# Sheet1.net
KiCad netlist of a schematic drawn in Altium Designer
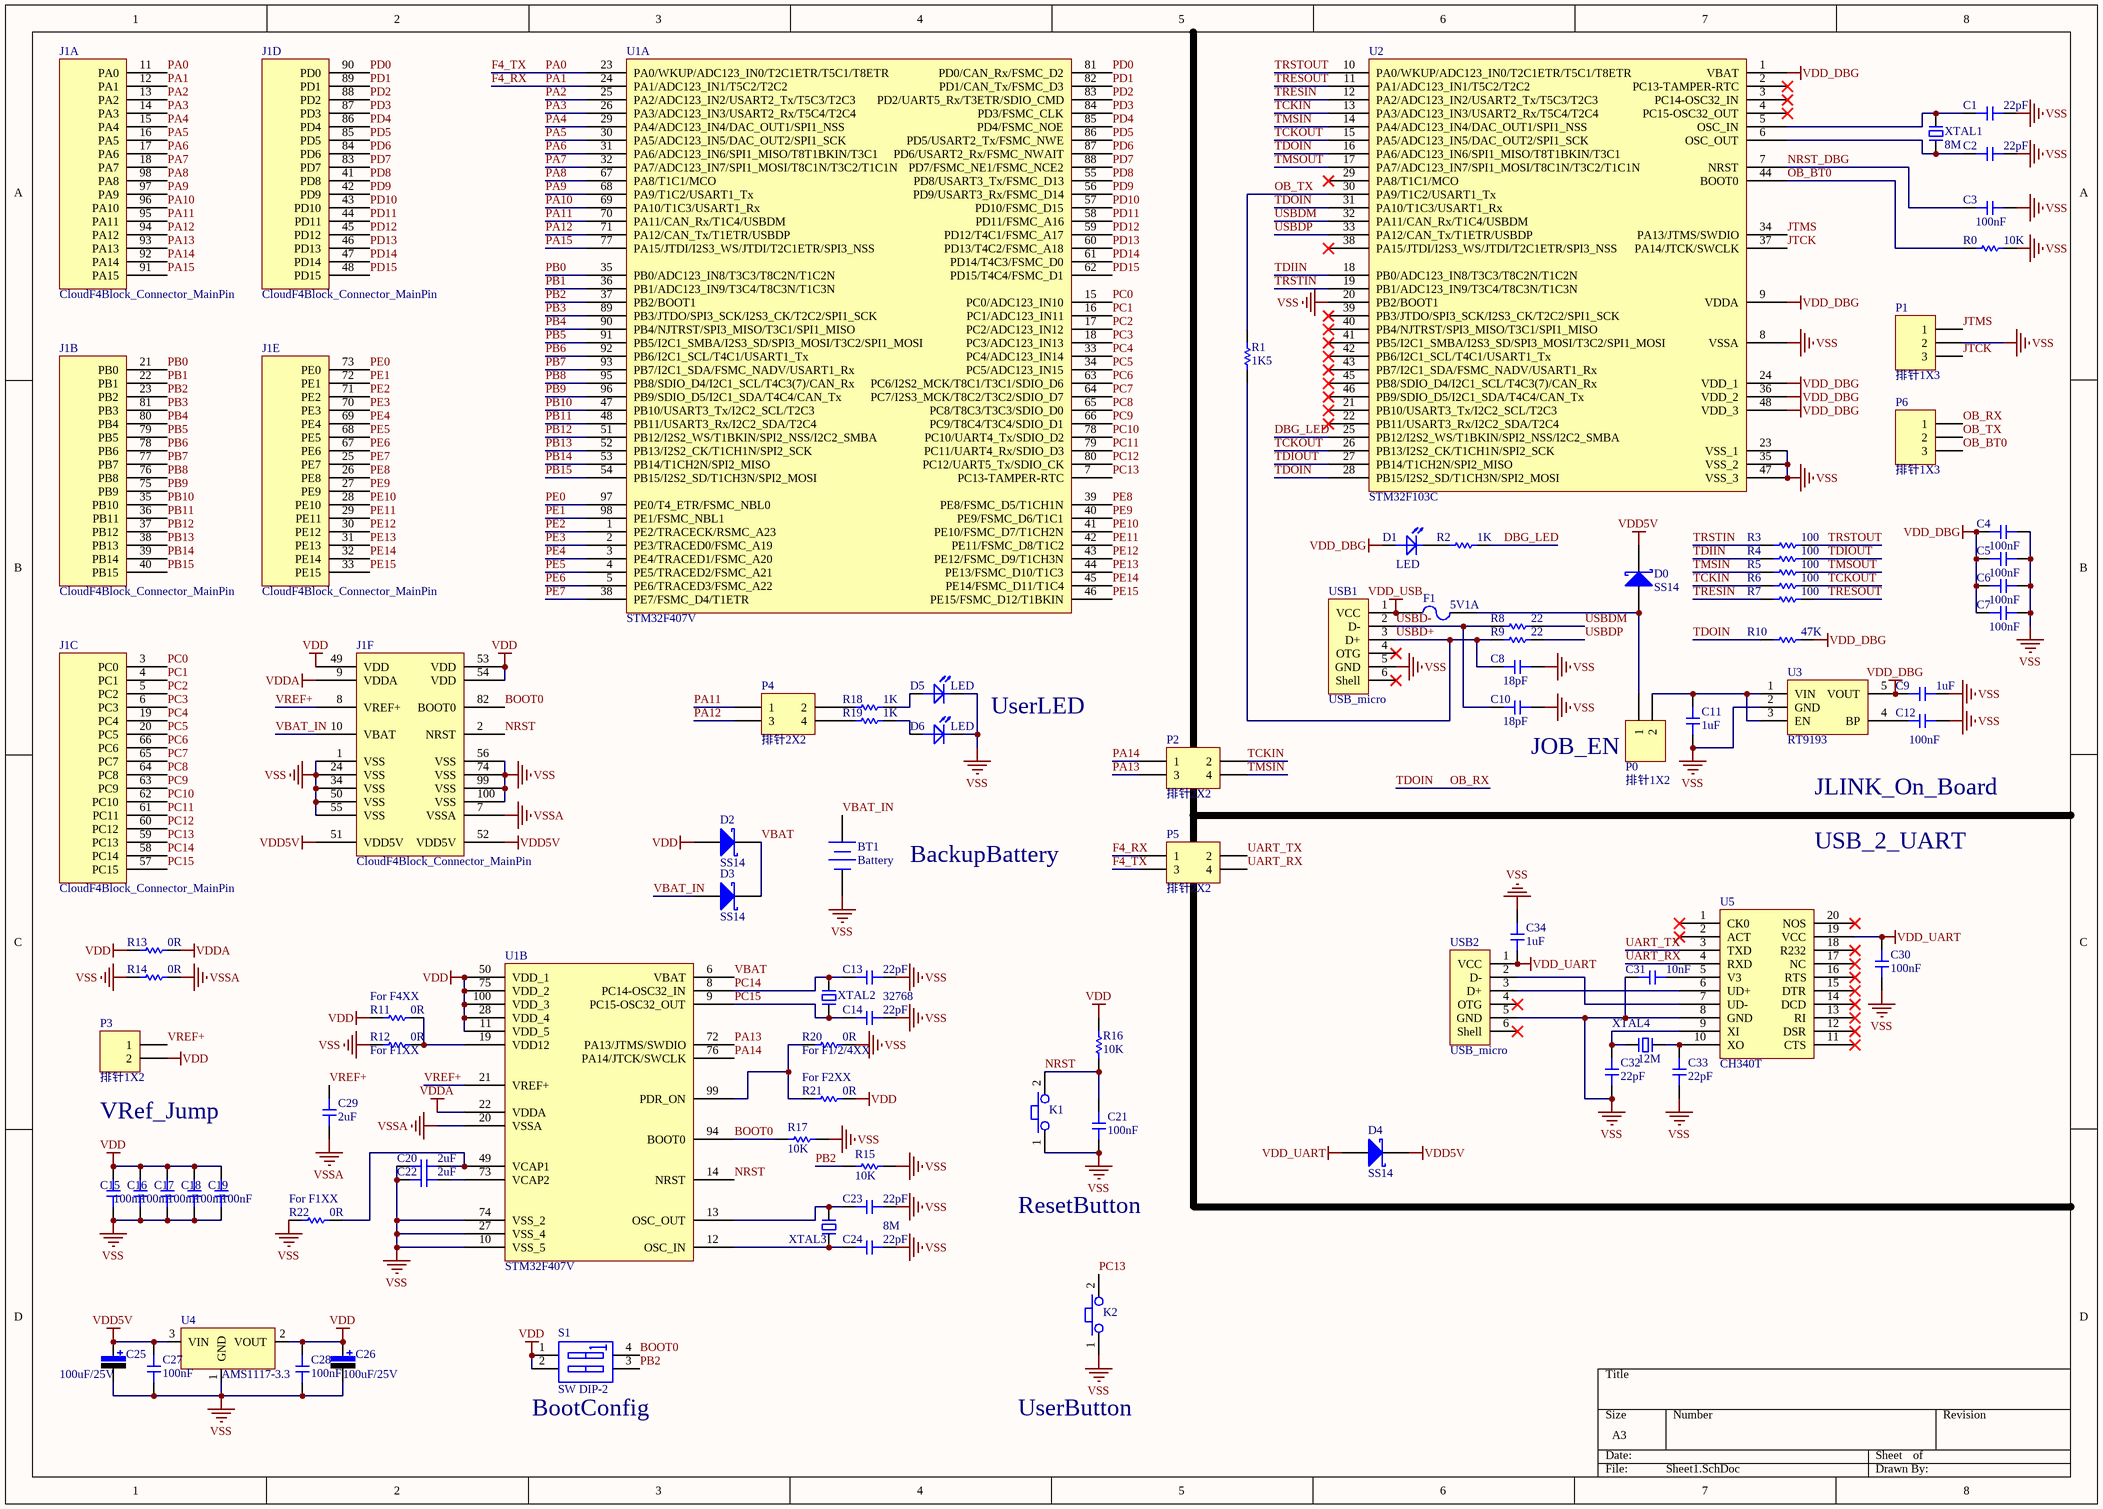
[diagram p0: Sheet1.SchDoc]

(export (version "E")
  (design (tool "Eeschema 10.0.6"))
  (components
    (comp (ref "BT1")
      (value "Battery")
      (footprint "CR1220")
      (description "CR1220纽扣电池座")
      (fields (field (name "PUBLISHER") "Altium Limited"))
      (libsource (lib "Miscellaneous Devices") (part "Battery"))
    )
    (comp (ref "C1")
      (value "22pF")
      (footprint "C-0603")
      (description "贴片电容0603")
      (fields (field (name "Comment") "Cap"))
      (libsource (lib "电阻电容电感") (part "Cap"))
    )
    (comp (ref "C2")
      (value "22pF")
      (footprint "C-0603")
      (description "贴片电容0603")
      (fields (field (name "Comment") "Cap"))
      (libsource (lib "电阻电容电感") (part "Cap"))
    )
    (comp (ref "C3")
      (value "100nF")
      (footprint "C-0603")
      (description "贴片电容0603")
      (fields (field (name "Comment") "Cap"))
      (libsource (lib "电阻电容电感") (part "Cap"))
    )
    (comp (ref "C4")
      (value "100nF")
      (footprint "C-0603")
      (description "贴片电容0603")
      (fields (field (name "Comment") "Cap"))
      (libsource (lib "电阻电容电感") (part "Cap"))
    )
    (comp (ref "C5")
      (value "100nF")
      (footprint "C-0603")
      (description "贴片电容0603")
      (fields (field (name "Comment") "Cap"))
      (libsource (lib "电阻电容电感") (part "Cap"))
    )
    (comp (ref "C6")
      (value "100nF")
      (footprint "C-0603")
      (description "贴片电容0603")
      (fields (field (name "Comment") "Cap"))
      (libsource (lib "电阻电容电感") (part "Cap"))
    )
    (comp (ref "C7")
      (value "100nF")
      (footprint "C-0603")
      (description "贴片电容0603")
      (fields (field (name "Comment") "Cap"))
      (libsource (lib "电阻电容电感") (part "Cap"))
    )
    (comp (ref "C8")
      (value "18pF")
      (footprint "C-0603")
      (description "贴片电容0603")
      (fields (field (name "Comment") "Cap"))
      (libsource (lib "电阻电容电感") (part "Cap"))
    )
    (comp (ref "C9")
      (value "1uF")
      (footprint "C-0805")
      (description "贴片电容0805")
      (fields (field (name "Comment") "Cap"))
      (libsource (lib "电阻电容电感") (part "Cap"))
    )
    (comp (ref "C10")
      (value "18pF")
      (footprint "C-0603")
      (description "贴片电容0603")
      (fields (field (name "Comment") "Cap"))
      (libsource (lib "电阻电容电感") (part "Cap"))
    )
    (comp (ref "C11")
      (value "1uF")
      (footprint "C-0805")
      (description "贴片电容0805")
      (fields (field (name "Comment") "Cap"))
      (libsource (lib "电阻电容电感") (part "Cap"))
    )
    (comp (ref "C12")
      (value "100nF")
      (footprint "C-0603")
      (description "贴片电容0603")
      (fields (field (name "Comment") "Cap"))
      (libsource (lib "电阻电容电感") (part "Cap"))
    )
    (comp (ref "C13")
      (value "22pF")
      (footprint "C-0603")
      (description "贴片电容0603")
      (fields (field (name "Comment") "Cap"))
      (libsource (lib "电阻电容电感") (part "Cap"))
    )
    (comp (ref "C14")
      (value "22pF")
      (footprint "C-0603")
      (description "贴片电容0603")
      (fields (field (name "Comment") "Cap"))
      (libsource (lib "电阻电容电感") (part "Cap"))
    )
    (comp (ref "C15")
      (value "100nF")
      (footprint "C-0603")
      (description "贴片电容0603")
      (fields (field (name "Comment") "Cap"))
      (libsource (lib "电阻电容电感") (part "Cap"))
    )
    (comp (ref "C16")
      (value "100nF")
      (footprint "C-0603")
      (description "贴片电容0603")
      (fields (field (name "Comment") "Cap"))
      (libsource (lib "电阻电容电感") (part "Cap"))
    )
    (comp (ref "C17")
      (value "100nF")
      (footprint "C-0603")
      (description "贴片电容0603")
      (fields (field (name "Comment") "Cap"))
      (libsource (lib "电阻电容电感") (part "Cap"))
    )
    (comp (ref "C18")
      (value "100nF")
      (footprint "C-0603")
      (description "贴片电容0603")
      (fields (field (name "Comment") "Cap"))
      (libsource (lib "电阻电容电感") (part "Cap"))
    )
    (comp (ref "C19")
      (value "100nF")
      (footprint "C-0603")
      (description "贴片电容0603")
      (fields (field (name "Comment") "Cap"))
      (libsource (lib "电阻电容电感") (part "Cap"))
    )
    (comp (ref "C20")
      (value "2uF")
      (footprint "C-0603")
      (description "贴片电容0603")
      (fields (field (name "Comment") "Cap"))
      (libsource (lib "电阻电容电感") (part "Cap"))
    )
    (comp (ref "C21")
      (value "100nF")
      (footprint "C-0603")
      (description "贴片电容0603")
      (fields (field (name "Comment") "Cap"))
      (libsource (lib "电阻电容电感") (part "Cap"))
    )
    (comp (ref "C22")
      (value "2uF")
      (footprint "C-0603")
      (description "贴片电容0603")
      (fields (field (name "Comment") "Cap"))
      (libsource (lib "电阻电容电感") (part "Cap"))
    )
    (comp (ref "C23")
      (value "22pF")
      (footprint "C-0603")
      (description "贴片电容0603")
      (fields (field (name "Comment") "Cap"))
      (libsource (lib "电阻电容电感") (part "Cap"))
    )
    (comp (ref "C24")
      (value "22pF")
      (footprint "C-0603")
      (description "贴片电容0603")
      (fields (field (name "Comment") "Cap"))
      (libsource (lib "电阻电容电感") (part "Cap"))
    )
    (comp (ref "C25")
      (value "100uF/25V")
      (footprint "C_TAN_C_6032")
      (description "钽电容C型")
      (fields (field (name "Comment") "Cap-Pol-ES") (field (name "PUBLISHER") "Altium Limited"))
      (libsource (lib "电阻电容电感") (part "Cap-Pol-ES"))
    )
    (comp (ref "C26")
      (value "100uF/25V")
      (footprint "C_TAN_C_6032")
      (description "钽电容C型")
      (fields (field (name "Comment") "Cap-Pol-ES") (field (name "PUBLISHER") "Altium Limited"))
      (libsource (lib "电阻电容电感") (part "Cap-Pol-ES"))
    )
    (comp (ref "C27")
      (value "100nF")
      (footprint "C-0603")
      (description "贴片电容0603")
      (fields (field (name "Comment") "Cap"))
      (libsource (lib "电阻电容电感") (part "Cap"))
    )
    (comp (ref "C28")
      (value "100nF")
      (footprint "C-0603")
      (description "贴片电容0603")
      (fields (field (name "Comment") "Cap"))
      (libsource (lib "电阻电容电感") (part "Cap"))
    )
    (comp (ref "C29")
      (value "2uF")
      (footprint "C-0603")
      (description "贴片电容0603")
      (fields (field (name "Comment") "Cap"))
      (libsource (lib "电阻电容电感") (part "Cap"))
    )
    (comp (ref "C30")
      (value "100nF")
      (footprint "C-0603")
      (description "贴片电容0603")
      (fields (field (name "Comment") "Cap"))
      (libsource (lib "电阻电容电感") (part "Cap"))
    )
    (comp (ref "C31")
      (value "10nF")
      (footprint "C-0603")
      (description "贴片电容0603")
      (fields (field (name "Comment") "Cap"))
      (libsource (lib "电阻电容电感") (part "Cap"))
    )
    (comp (ref "C32")
      (value "22pF")
      (footprint "C-0603")
      (description "贴片电容0603")
      (fields (field (name "Comment") "Cap"))
      (libsource (lib "电阻电容电感") (part "Cap"))
    )
    (comp (ref "C33")
      (value "22pF")
      (footprint "C-0603")
      (description "贴片电容0603")
      (fields (field (name "Comment") "Cap"))
      (libsource (lib "电阻电容电感") (part "Cap"))
    )
    (comp (ref "C34")
      (value "1uF")
      (footprint "C-0603")
      (description "贴片电容0603")
      (fields (field (name "Comment") "Cap"))
      (libsource (lib "电阻电容电感") (part "Cap"))
    )
    (comp (ref "D0")
      (value "SS14")
      (footprint "SOD123")
      (description "1N5819肖特基SDO123")
      (fields (field (name "PUBLISHER") "Altium Limited"))
      (libsource (lib "Cloud_AD_Integrated") (part "D Schottky"))
    )
    (comp (ref "D1")
      (value "LED")
      (footprint "0603LED_RED")
      (description "红色LED 0603")
      (libsource (lib "二极管") (part "LED"))
    )
    (comp (ref "D2")
      (value "SS14")
      (footprint "SOD123")
      (description "1N5819肖特基SDO123")
      (fields (field (name "PUBLISHER") "Altium Limited"))
      (libsource (lib "Cloud_AD_Integrated") (part "D Schottky"))
    )
    (comp (ref "D3")
      (value "SS14")
      (footprint "SOD123")
      (description "1N5819肖特基SDO123")
      (fields (field (name "PUBLISHER") "Altium Limited"))
      (libsource (lib "Cloud_AD_Integrated") (part "D Schottky"))
    )
    (comp (ref "D4")
      (value "SS14")
      (footprint "SOD123")
      (description "1N5819肖特基SDO123")
      (fields (field (name "PUBLISHER") "Altium Limited"))
      (libsource (lib "Cloud_AD_Integrated") (part "D Schottky"))
    )
    (comp (ref "D5")
      (value "LED")
      (footprint "0603LED_GREEN")
      (description "绿色LED 0603")
      (libsource (lib "二极管") (part "LED"))
    )
    (comp (ref "D6")
      (value "LED")
      (footprint "0603LED_YELLOW")
      (description "红色LED 0603")
      (libsource (lib "二极管") (part "LED"))
    )
    (comp (ref "F1")
      (value "5V1A")
      (footprint "F-1812")
      (description "1.5A自恢复保险丝 1812")
      (fields (field (name "Comment") "自恢复保险丝"))
      (libsource (lib "电阻电容电感") (part "自恢复保险丝"))
    )
    (comp (ref "J1")
      (value "CloudF4Block_Connector_MainPin")
      (footprint "CloudF4BlockConnector")
      (description "25X2双排排母插座 2个")
      (libsource (lib "接插件") (part "CloudF4Block_Connector_MainPin"))
    )
    (comp (ref "K1")
      (value "BUTTON_2PIN")
      (footprint "TS017")
      (description "TS-017贴片侧边按键")
      (libsource (lib "开关按钮") (part "BUTTON_2PIN"))
    )
    (comp (ref "K2")
      (value "BUTTON_2PIN")
      (footprint "TS017")
      (description "TS-017贴片侧边按键")
      (libsource (lib "开关按钮") (part "BUTTON_2PIN"))
    )
    (comp (ref "P0") (value "排针1X2") (footprint "IDC1x2-2.54") (libsource (lib "") (part "排针1X2_1")))
    (comp (ref "P1")
      (value "排针1X3")
      (footprint "IDC1x3-2.54")
      (libsource (lib "Cloud_AD_Integrated") (part "排针1X3"))
    )
    (comp (ref "P2")
      (value "排针2X2")
      (footprint "IDC2x2-2.54")
      (libsource (lib "Cloud_AD_Integrated") (part "排针2X2"))
    )
    (comp (ref "P3")
      (value "排针1X2")
      (footprint "IDC1x2-2.54")
      (libsource (lib "Cloud_AD_Integrated") (part "排针1X2"))
    )
    (comp (ref "P4")
      (value "排针2X2")
      (footprint "IDC2x2-2.54")
      (libsource (lib "Cloud_AD_Integrated") (part "排针2X2"))
    )
    (comp (ref "P5")
      (value "排针2X2")
      (footprint "IDC2x2-2.54")
      (libsource (lib "Cloud_AD_Integrated") (part "排针2X2"))
    )
    (comp (ref "P6")
      (value "排针1X3")
      (footprint "IDC1x3-2.54")
      (libsource (lib "Cloud_AD_Integrated") (part "排针1X3"))
    )
    (comp (ref "R0")
      (value "10K")
      (footprint "R-0603")
      (description "贴片电阻0603")
      (fields (field (name "Comment") "RES"))
      (libsource (lib "电阻电容电感") (part "RES"))
    )
    (comp (ref "R1")
      (value "1K5")
      (footprint "R-0603")
      (description "贴片电阻0603")
      (fields (field (name "Comment") "RES"))
      (libsource (lib "电阻电容电感") (part "RES"))
    )
    (comp (ref "R2")
      (value "1K")
      (footprint "R-0603")
      (description "贴片电阻0603")
      (fields (field (name "Comment") "RES"))
      (libsource (lib "电阻电容电感") (part "RES"))
    )
    (comp (ref "R3")
      (value "100")
      (footprint "R-0603")
      (description "贴片电阻0603")
      (fields (field (name "Comment") "RES"))
      (libsource (lib "电阻电容电感") (part "RES"))
    )
    (comp (ref "R4")
      (value "100")
      (footprint "R-0603")
      (description "贴片电阻0603")
      (fields (field (name "Comment") "RES"))
      (libsource (lib "电阻电容电感") (part "RES"))
    )
    (comp (ref "R5")
      (value "100")
      (footprint "R-0603")
      (description "贴片电阻0603")
      (fields (field (name "Comment") "RES"))
      (libsource (lib "电阻电容电感") (part "RES"))
    )
    (comp (ref "R6")
      (value "100")
      (footprint "R-0603")
      (description "贴片电阻0603")
      (fields (field (name "Comment") "RES"))
      (libsource (lib "电阻电容电感") (part "RES"))
    )
    (comp (ref "R7")
      (value "100")
      (footprint "R-0603")
      (description "贴片电阻0603")
      (fields (field (name "Comment") "RES"))
      (libsource (lib "电阻电容电感") (part "RES"))
    )
    (comp (ref "R8")
      (value "22")
      (footprint "R-0603")
      (description "贴片电阻0603")
      (fields (field (name "Comment") "RES"))
      (libsource (lib "电阻电容电感") (part "RES"))
    )
    (comp (ref "R9")
      (value "22")
      (footprint "R-0603")
      (description "贴片电阻0603")
      (fields (field (name "Comment") "RES"))
      (libsource (lib "电阻电容电感") (part "RES"))
    )
    (comp (ref "R10")
      (value "47K")
      (footprint "R-0603")
      (description "贴片电阻0603")
      (fields (field (name "Comment") "RES"))
      (libsource (lib "电阻电容电感") (part "RES"))
    )
    (comp (ref "R11")
      (value "0R")
      (footprint "R-0603")
      (description "贴片电阻0603")
      (fields (field (name "Comment") "RES"))
      (libsource (lib "电阻电容电感") (part "RES"))
    )
    (comp (ref "R12")
      (value "0R")
      (footprint "R-0603")
      (description "贴片电阻0603")
      (fields (field (name "Comment") "RES"))
      (libsource (lib "电阻电容电感") (part "RES"))
    )
    (comp (ref "R13")
      (value "0R")
      (footprint "R-0603")
      (description "贴片电阻0603")
      (fields (field (name "Comment") "RES"))
      (libsource (lib "电阻电容电感") (part "RES"))
    )
    (comp (ref "R14")
      (value "0R")
      (footprint "R-0603")
      (description "贴片电阻0603")
      (fields (field (name "Comment") "RES"))
      (libsource (lib "电阻电容电感") (part "RES"))
    )
    (comp (ref "R15")
      (value "10K")
      (footprint "R-0603")
      (description "贴片电阻0603")
      (fields (field (name "Comment") "RES"))
      (libsource (lib "电阻电容电感") (part "RES"))
    )
    (comp (ref "R16")
      (value "10K")
      (footprint "R-0603")
      (description "贴片电阻0603")
      (fields (field (name "Comment") "RES"))
      (libsource (lib "电阻电容电感") (part "RES"))
    )
    (comp (ref "R17")
      (value "10K")
      (footprint "R-0603")
      (description "贴片电阻0603")
      (fields (field (name "Comment") "RES"))
      (libsource (lib "电阻电容电感") (part "RES"))
    )
    (comp (ref "R18")
      (value "1K")
      (footprint "R-0603")
      (description "贴片电阻0603")
      (fields (field (name "Comment") "RES"))
      (libsource (lib "电阻电容电感") (part "RES"))
    )
    (comp (ref "R19")
      (value "1K")
      (footprint "R-0603")
      (description "贴片电阻0603")
      (fields (field (name "Comment") "RES"))
      (libsource (lib "电阻电容电感") (part "RES"))
    )
    (comp (ref "R20")
      (value "0R")
      (footprint "R-0603")
      (description "贴片电阻0603")
      (fields (field (name "Comment") "RES"))
      (libsource (lib "电阻电容电感") (part "RES"))
    )
    (comp (ref "R21")
      (value "0R")
      (footprint "R-0603")
      (description "贴片电阻0603")
      (fields (field (name "Comment") "RES"))
      (libsource (lib "电阻电容电感") (part "RES"))
    )
    (comp (ref "R22")
      (value "0R")
      (footprint "R-0603")
      (description "贴片电阻0603")
      (fields (field (name "Comment") "RES"))
      (libsource (lib "电阻电容电感") (part "RES"))
    )
    (comp (ref "S1")
      (value "SW DIP-2")
      (footprint "KEY-DIP-2-SMD")
      (description "2X2编码开关")
      (fields (field (name "PUBLISHER") "Altium Limited"))
      (libsource (lib "Cloud_AD_Integrated") (part "SW DIP-2"))
    )
    (comp (ref "U1")
      (value "STM32F407V")
      (footprint "TQFP100")
      (description "STM32F407VGT6")
      (libsource (lib "Cloud_AD_Integrated") (part "STM32F407V"))
    )
    (comp (ref "U2")
      (value "STM32F103C")
      (footprint "TQFP48")
      (description "STM32F103C8T6")
      (libsource (lib "Cloud_AD_Integrated") (part "STM32F103C"))
    )
    (comp (ref "U3")
      (value "RT9193")
      (footprint "SOT23-5")
      (description "3.3V LDO")
      (libsource (lib "Cloud_AD_Integrated") (part "RT9193"))
    )
    (comp (ref "U4")
      (value "AMS1117-3.3")
      (footprint "AMS1117")
      (libsource (lib "Cloud_AD_Integrated") (part "AMS1117-3.3"))
    )
    (comp (ref "U5")
      (value "CH340T")
      (footprint "SSOP20")
      (description "CH340T USB转串口")
      (libsource (lib "Cloud_AD_Integrated") (part "CH340T"))
    )
    (comp (ref "USB1")
      (value "USB_micro")
      (footprint "USB_Micro")
      (description "MicroUSB贴片座")
      (libsource (lib "Cloud_AD_Integrated") (part "USB_micro"))
    )
    (comp (ref "USB2")
      (value "USB_micro")
      (footprint "USB_Micro")
      (description "MicroUSB贴片座")
      (libsource (lib "Cloud_AD_Integrated") (part "USB_micro"))
    )
    (comp (ref "XTAL1")
      (value "8M")
      (footprint "XTAL-5032-2P")
      (description "无源晶振5032")
      (fields (field (name "Comment") "无源晶振_2Pin"))
      (libsource (lib "晶振") (part "无源晶振_2Pin"))
    )
    (comp (ref "XTAL2")
      (value "32768")
      (footprint "XTAL_2X6 - SM")
      (description "无源晶振32768圆柱")
      (fields (field (name "Comment") "无源晶振_2Pin"))
      (libsource (lib "晶振") (part "无源晶振_2Pin"))
    )
    (comp (ref "XTAL3")
      (value "8M")
      (footprint "XTAL-5032-2P")
      (description "无源晶振5032")
      (fields (field (name "Comment") "无源晶振_2Pin"))
      (libsource (lib "晶振") (part "无源晶振_2Pin"))
    )
    (comp (ref "XTAL4")
      (value "12M")
      (footprint "XTAL-5032-2P")
      (description "无源晶振5032")
      (fields (field (name "Comment") "无源晶振_2Pin"))
      (libsource (lib "晶振") (part "无源晶振_2Pin"))
    )
  )
  (nets
    (net (code "1") (name "/BOOT0") (class "Default")
      (node (ref "J1") (pin "82") (pinfunction "BOOT0_82") (pintype "passive"))
      (node (ref "R17") (pin "2") (pinfunction "2_2") (pintype "passive"))
      (node (ref "S1") (pin "4") (pinfunction "A4_4") (pintype "passive"))
      (node (ref "U1") (pin "94") (pinfunction "BOOT0_94") (pintype "passive"))
    )
    (net (code "2") (name "/DBG_LED") (class "Default")
      (node (ref "R2") (pin "2") (pinfunction "2_2") (pintype "passive"))
      (node (ref "U2") (pin "25") (pinfunction "PB12/I2S2_WS/T1BKIN/SPI2_NSS/I2C2_SMBA_25") (pintype "passive"))
    )
    (net (code "3") (name "/F4_RX") (class "Default")
      (node (ref "J1") (pin "12") (pinfunction "PA1_12") (pintype "passive"))
      (node (ref "P5") (pin "1") (pinfunction "1_1") (pintype "passive"))
      (node (ref "U1") (pin "24") (pinfunction "PA1/ADC123_IN1/T5C2/T2C2_24") (pintype "passive"))
    )
    (net (code "4") (name "/F4_TX") (class "Default")
      (node (ref "J1") (pin "11") (pinfunction "PA0_11") (pintype "passive"))
      (node (ref "P5") (pin "3") (pinfunction "3_3") (pintype "passive"))
      (node (ref "U1") (pin "23") (pinfunction "PA0/WKUP/ADC123_IN0/T2C1ETR/T5C1/T8ETR_23") (pintype "passive"))
    )
    (net (code "5") (name "/JTCK") (class "Default")
      (node (ref "P1") (pin "3") (pinfunction "3_3") (pintype "passive"))
      (node (ref "U2") (pin "37") (pinfunction "PA14/JTCK/SWCLK_37") (pintype "passive"))
    )
    (net (code "6") (name "/JTMS") (class "Default")
      (node (ref "P1") (pin "1") (pinfunction "1_1") (pintype "passive"))
      (node (ref "U2") (pin "34") (pinfunction "PA13/JTMS/SWDIO_34") (pintype "passive"))
    )
    (net (code "7") (name "/NRST") (class "Default")
      (node (ref "C21") (pin "1") (pinfunction "1_1") (pintype "passive"))
      (node (ref "J1") (pin "2") (pinfunction "NRST_2") (pintype "passive"))
      (node (ref "K1") (pin "2") (pinfunction "2_2") (pintype "passive"))
      (node (ref "R16") (pin "2") (pinfunction "2_2") (pintype "passive"))
      (node (ref "U1") (pin "14") (pinfunction "NRST_14") (pintype "passive"))
    )
    (net (code "8") (name "/NRST_DBG") (class "Default")
      (node (ref "C3") (pin "1") (pinfunction "1_1") (pintype "passive"))
      (node (ref "U2") (pin "7") (pinfunction "NRST_7") (pintype "passive"))
    )
    (net (code "9") (name "/OB_BT0") (class "Default")
      (node (ref "P6") (pin "3") (pinfunction "3_3") (pintype "passive"))
      (node (ref "R0") (pin "1") (pinfunction "1_1") (pintype "passive"))
      (node (ref "U2") (pin "44") (pinfunction "BOOT0_44") (pintype "passive"))
    )
    (net (code "10") (name "/OB_RX") (class "Default")
      (node (ref "P6") (pin "1") (pinfunction "1_1") (pintype "passive"))
      (node (ref "R10") (pin "1") (pinfunction "1_1") (pintype "passive"))
      (node (ref "U2") (pin "16") (pinfunction "PA6/ADC123_IN6/SPI1_MISO/T8T1BKIN/T3C1_16") (pintype "passive"))
      (node (ref "U2") (pin "28") (pinfunction "PB15/I2S2_SD/T1CH3N/SPI2_MOSI_28") (pintype "passive"))
      (node (ref "U2") (pin "31") (pinfunction "PA10/T1C3/USART1_Rx_31") (pintype "passive"))
    )
    (net (code "11") (name "/OB_TX") (class "Default")
      (node (ref "P6") (pin "2") (pinfunction "2_2") (pintype "passive"))
      (node (ref "R1") (pin "2") (pinfunction "2_2") (pintype "passive"))
      (node (ref "U2") (pin "30") (pinfunction "PA9/T1C2/USART1_Tx_30") (pintype "passive"))
    )
    (net (code "12") (name "/PA2") (class "Default")
      (node (ref "J1") (pin "13") (pinfunction "PA2_13") (pintype "passive"))
      (node (ref "U1") (pin "25") (pinfunction "PA2/ADC123_IN2/USART2_Tx/T5C3/T2C3_25") (pintype "passive"))
    )
    (net (code "13") (name "/PA3") (class "Default")
      (node (ref "J1") (pin "14") (pinfunction "PA3_14") (pintype "passive"))
      (node (ref "U1") (pin "26") (pinfunction "PA3/ADC123_IN3/USART2_Rx/T5C4/T2C4_26") (pintype "passive"))
    )
    (net (code "14") (name "/PA4") (class "Default")
      (node (ref "J1") (pin "15") (pinfunction "PA4_15") (pintype "passive"))
      (node (ref "U1") (pin "29") (pinfunction "PA4/ADC123_IN4/DAC_OUT1/SPI1_NSS_29") (pintype "passive"))
    )
    (net (code "15") (name "/PA5") (class "Default")
      (node (ref "J1") (pin "16") (pinfunction "PA5_16") (pintype "passive"))
      (node (ref "U1") (pin "30") (pinfunction "PA5/ADC123_IN5/DAC_OUT2/SPI1_SCK_30") (pintype "passive"))
    )
    (net (code "16") (name "/PA6") (class "Default")
      (node (ref "J1") (pin "17") (pinfunction "PA6_17") (pintype "passive"))
      (node (ref "U1") (pin "31") (pinfunction "PA6/ADC123_IN6/SPI1_MISO/T8T1BKIN/T3C1_31") (pintype "passive"))
    )
    (net (code "17") (name "/PA7") (class "Default")
      (node (ref "J1") (pin "18") (pinfunction "PA7_18") (pintype "passive"))
      (node (ref "U1") (pin "32") (pinfunction "PA7/ADC123_IN7/SPI1_MOSI/T8C1N/T3C2/T1C1N_32") (pintype "passive"))
    )
    (net (code "18") (name "/PA8") (class "Default")
      (node (ref "J1") (pin "98") (pinfunction "PA8_98") (pintype "passive"))
      (node (ref "U1") (pin "67") (pinfunction "PA8/T1C1/MCO_67") (pintype "passive"))
    )
    (net (code "19") (name "/PA9") (class "Default")
      (node (ref "J1") (pin "97") (pinfunction "PA9_97") (pintype "passive"))
      (node (ref "U1") (pin "68") (pinfunction "PA9/T1C2/USART1_Tx_68") (pintype "passive"))
    )
    (net (code "20") (name "/PA10") (class "Default")
      (node (ref "J1") (pin "96") (pinfunction "PA10_96") (pintype "passive"))
      (node (ref "U1") (pin "69") (pinfunction "PA10/T1C3/USART1_Rx_69") (pintype "passive"))
    )
    (net (code "21") (name "/PA11") (class "Default")
      (node (ref "J1") (pin "95") (pinfunction "PA11_95") (pintype "passive"))
      (node (ref "P4") (pin "1") (pinfunction "1_1") (pintype "passive"))
      (node (ref "U1") (pin "70") (pinfunction "PA11/CAN_Rx/T1C4/USBDM_70") (pintype "passive"))
    )
    (net (code "22") (name "/PA12") (class "Default")
      (node (ref "J1") (pin "94") (pinfunction "PA12_94") (pintype "passive"))
      (node (ref "P4") (pin "3") (pinfunction "3_3") (pintype "passive"))
      (node (ref "U1") (pin "71") (pinfunction "PA12/CAN_Tx/T1ETR/USBDP_71") (pintype "passive"))
    )
    (net (code "23") (name "/PA13") (class "Default")
      (node (ref "J1") (pin "93") (pinfunction "PA13_93") (pintype "passive"))
      (node (ref "P2") (pin "3") (pinfunction "3_3") (pintype "passive"))
      (node (ref "U1") (pin "72") (pinfunction "PA13/JTMS/SWDIO_72") (pintype "passive"))
    )
    (net (code "24") (name "/PA14") (class "Default")
      (node (ref "J1") (pin "92") (pinfunction "PA14_92") (pintype "passive"))
      (node (ref "P2") (pin "1") (pinfunction "1_1") (pintype "passive"))
      (node (ref "U1") (pin "76") (pinfunction "PA14/JTCK/SWCLK_76") (pintype "passive"))
    )
    (net (code "25") (name "/PA15") (class "Default")
      (node (ref "J1") (pin "91") (pinfunction "PA15_91") (pintype "passive"))
      (node (ref "U1") (pin "77") (pinfunction "PA15/JTDI/I2S3_WS/JTDI/T2C1ETR/SPI3_NSS_77") (pintype "passive"))
    )
    (net (code "26") (name "/PB0") (class "Default")
      (node (ref "J1") (pin "21") (pinfunction "PB0_21") (pintype "passive"))
      (node (ref "U1") (pin "35") (pinfunction "PB0/ADC123_IN8/T3C3/T8C2N/T1C2N_35") (pintype "passive"))
    )
    (net (code "27") (name "/PB1") (class "Default")
      (node (ref "J1") (pin "22") (pinfunction "PB1_22") (pintype "passive"))
      (node (ref "U1") (pin "36") (pinfunction "PB1/ADC123_IN9/T3C4/T8C3N/T1C3N_36") (pintype "passive"))
    )
    (net (code "28") (name "/PB2") (class "Default")
      (node (ref "J1") (pin "23") (pinfunction "PB2_23") (pintype "passive"))
      (node (ref "R15") (pin "2") (pinfunction "2_2") (pintype "passive"))
      (node (ref "S1") (pin "3") (pinfunction "A3_3") (pintype "passive"))
      (node (ref "U1") (pin "37") (pinfunction "PB2/BOOT1_37") (pintype "passive"))
    )
    (net (code "29") (name "/PB3") (class "Default")
      (node (ref "J1") (pin "81") (pinfunction "PB3_81") (pintype "passive"))
      (node (ref "U1") (pin "89") (pinfunction "PB3/JTDO/SPI3_SCK/I2S3_CK/T2C2/SPI1_SCK_89") (pintype "passive"))
    )
    (net (code "30") (name "/PB4") (class "Default")
      (node (ref "J1") (pin "80") (pinfunction "PB4_80") (pintype "passive"))
      (node (ref "U1") (pin "90") (pinfunction "PB4/NJTRST/SPI3_MISO/T3C1/SPI1_MISO_90") (pintype "passive"))
    )
    (net (code "31") (name "/PB5") (class "Default")
      (node (ref "J1") (pin "79") (pinfunction "PB5_79") (pintype "passive"))
      (node (ref "U1") (pin "91") (pinfunction "PB5/I2C1_SMBA/I2S3_SD/SPI3_MOSI/T3C2/SPI1_MOSI_91") (pintype "passive"))
    )
    (net (code "32") (name "/PB6") (class "Default")
      (node (ref "J1") (pin "78") (pinfunction "PB6_78") (pintype "passive"))
      (node (ref "U1") (pin "92") (pinfunction "PB6/I2C1_SCL/T4C1/USART1_Tx_92") (pintype "passive"))
    )
    (net (code "33") (name "/PB7") (class "Default")
      (node (ref "J1") (pin "77") (pinfunction "PB7_77") (pintype "passive"))
      (node (ref "U1") (pin "93") (pinfunction "PB7/I2C1_SDA/FSMC_NADV/USART1_Rx_93") (pintype "passive"))
    )
    (net (code "34") (name "/PB8") (class "Default")
      (node (ref "J1") (pin "76") (pinfunction "PB8_76") (pintype "passive"))
      (node (ref "U1") (pin "95") (pinfunction "PB8/SDIO_D4/I2C1_SCL/T4C3(7)/CAN_Rx_95") (pintype "passive"))
    )
    (net (code "35") (name "/PB9") (class "Default")
      (node (ref "J1") (pin "75") (pinfunction "PB9_75") (pintype "passive"))
      (node (ref "U1") (pin "96") (pinfunction "PB9/SDIO_D5/I2C1_SDA/T4C4/CAN_Tx_96") (pintype "passive"))
    )
    (net (code "36") (name "/PB10") (class "Default")
      (node (ref "J1") (pin "35") (pinfunction "PB10_35") (pintype "passive"))
      (node (ref "U1") (pin "47") (pinfunction "PB10/USART3_Tx/I2C2_SCL/T2C3_47") (pintype "passive"))
    )
    (net (code "37") (name "/PB11") (class "Default")
      (node (ref "J1") (pin "36") (pinfunction "PB11_36") (pintype "passive"))
      (node (ref "U1") (pin "48") (pinfunction "PB11/USART3_Rx/I2C2_SDA/T2C4_48") (pintype "passive"))
    )
    (net (code "38") (name "/PB12") (class "Default")
      (node (ref "J1") (pin "37") (pinfunction "PB12_37") (pintype "passive"))
      (node (ref "U1") (pin "51") (pinfunction "PB12/I2S2_WS/T1BKIN/SPI2_NSS/I2C2_SMBA_51") (pintype "passive"))
    )
    (net (code "39") (name "/PB13") (class "Default")
      (node (ref "J1") (pin "38") (pinfunction "PB13_38") (pintype "passive"))
      (node (ref "U1") (pin "52") (pinfunction "PB13/I2S2_CK/T1CH1N/SPI2_SCK_52") (pintype "passive"))
    )
    (net (code "40") (name "/PB14") (class "Default")
      (node (ref "J1") (pin "39") (pinfunction "PB14_39") (pintype "passive"))
      (node (ref "U1") (pin "53") (pinfunction "PB14/T1CH2N/SPI2_MISO_53") (pintype "passive"))
    )
    (net (code "41") (name "/PB15") (class "Default")
      (node (ref "J1") (pin "40") (pinfunction "PB15_40") (pintype "passive"))
      (node (ref "U1") (pin "54") (pinfunction "PB15/I2S2_SD/T1CH3N/SPI2_MOSI_54") (pintype "passive"))
    )
    (net (code "42") (name "/PC0") (class "Default")
      (node (ref "J1") (pin "3") (pinfunction "PC0_3") (pintype "passive"))
      (node (ref "U1") (pin "15") (pinfunction "PC0/ADC123_IN10_15") (pintype "passive"))
    )
    (net (code "43") (name "/PC1") (class "Default")
      (node (ref "J1") (pin "4") (pinfunction "PC1_4") (pintype "passive"))
      (node (ref "U1") (pin "16") (pinfunction "PC1/ADC123_IN11_16") (pintype "passive"))
    )
    (net (code "44") (name "/PC2") (class "Default")
      (node (ref "J1") (pin "5") (pinfunction "PC2_5") (pintype "passive"))
      (node (ref "U1") (pin "17") (pinfunction "PC2/ADC123_IN12_17") (pintype "passive"))
    )
    (net (code "45") (name "/PC3") (class "Default")
      (node (ref "J1") (pin "6") (pinfunction "PC3_6") (pintype "passive"))
      (node (ref "U1") (pin "18") (pinfunction "PC3/ADC123_IN13_18") (pintype "passive"))
    )
    (net (code "46") (name "/PC4") (class "Default")
      (node (ref "J1") (pin "19") (pinfunction "PC4_19") (pintype "passive"))
      (node (ref "U1") (pin "33") (pinfunction "PC4/ADC123_IN14_33") (pintype "passive"))
    )
    (net (code "47") (name "/PC5") (class "Default")
      (node (ref "J1") (pin "20") (pinfunction "PC5_20") (pintype "passive"))
      (node (ref "U1") (pin "34") (pinfunction "PC5/ADC123_IN15_34") (pintype "passive"))
    )
    (net (code "48") (name "/PC6") (class "Default")
      (node (ref "J1") (pin "66") (pinfunction "PC6_66") (pintype "passive"))
      (node (ref "U1") (pin "63") (pinfunction "PC6/I2S2_MCK/T8C1/T3C1/SDIO_D6_63") (pintype "passive"))
    )
    (net (code "49") (name "/PC7") (class "Default")
      (node (ref "J1") (pin "65") (pinfunction "PC7_65") (pintype "passive"))
      (node (ref "U1") (pin "64") (pinfunction "PC7/I2S3_MCK/T8C2/T3C2/SDIO_D7_64") (pintype "passive"))
    )
    (net (code "50") (name "/PC8") (class "Default")
      (node (ref "J1") (pin "64") (pinfunction "PC8_64") (pintype "passive"))
      (node (ref "U1") (pin "65") (pinfunction "PC8/T8C3/T3C3/SDIO_D0_65") (pintype "passive"))
    )
    (net (code "51") (name "/PC9") (class "Default")
      (node (ref "J1") (pin "63") (pinfunction "PC9_63") (pintype "passive"))
      (node (ref "U1") (pin "66") (pinfunction "PC9/T8C4/T3C4/SDIO_D1_66") (pintype "passive"))
    )
    (net (code "52") (name "/PC10") (class "Default")
      (node (ref "J1") (pin "62") (pinfunction "PC10_62") (pintype "passive"))
      (node (ref "U1") (pin "78") (pinfunction "PC10/UART4_Tx/SDIO_D2_78") (pintype "passive"))
    )
    (net (code "53") (name "/PC11") (class "Default")
      (node (ref "J1") (pin "61") (pinfunction "PC11_61") (pintype "passive"))
      (node (ref "U1") (pin "79") (pinfunction "PC11/UART4_Rx/SDIO_D3_79") (pintype "passive"))
    )
    (net (code "54") (name "/PC12") (class "Default")
      (node (ref "J1") (pin "60") (pinfunction "PC12_60") (pintype "passive"))
      (node (ref "U1") (pin "80") (pinfunction "PC12/UART5_Tx/SDIO_CK_80") (pintype "passive"))
    )
    (net (code "55") (name "/PC13") (class "Default")
      (node (ref "J1") (pin "59") (pinfunction "PC13_59") (pintype "passive"))
      (node (ref "K2") (pin "2") (pinfunction "2_2") (pintype "passive"))
      (node (ref "U1") (pin "7") (pinfunction "PC13-TAMPER-RTC_7") (pintype "passive"))
    )
    (net (code "56") (name "/PC14") (class "Default")
      (node (ref "C13") (pin "1") (pinfunction "1_1") (pintype "passive"))
      (node (ref "J1") (pin "58") (pinfunction "PC14_58") (pintype "passive"))
      (node (ref "U1") (pin "8") (pinfunction "PC14-OSC32_IN_8") (pintype "passive"))
      (node (ref "XTAL2") (pin "1") (pinfunction "1_1") (pintype "passive"))
    )
    (net (code "57") (name "/PC15") (class "Default")
      (node (ref "C14") (pin "1") (pinfunction "1_1") (pintype "passive"))
      (node (ref "J1") (pin "57") (pinfunction "PC15_57") (pintype "passive"))
      (node (ref "U1") (pin "9") (pinfunction "PC15-OSC32_OUT_9") (pintype "passive"))
      (node (ref "XTAL2") (pin "2") (pinfunction "2_2") (pintype "passive"))
    )
    (net (code "58") (name "/PD0") (class "Default")
      (node (ref "J1") (pin "90") (pinfunction "PD0_90") (pintype "passive"))
      (node (ref "U1") (pin "81") (pinfunction "PD0/CAN_Rx/FSMC_D2_81") (pintype "passive"))
    )
    (net (code "59") (name "/PD1") (class "Default")
      (node (ref "J1") (pin "89") (pinfunction "PD1_89") (pintype "passive"))
      (node (ref "U1") (pin "82") (pinfunction "PD1/CAN_Tx/FSMC_D3_82") (pintype "passive"))
    )
    (net (code "60") (name "/PD2") (class "Default")
      (node (ref "J1") (pin "88") (pinfunction "PD2_88") (pintype "passive"))
      (node (ref "U1") (pin "83") (pinfunction "PD2/UART5_Rx/T3ETR/SDIO_CMD_83") (pintype "passive"))
    )
    (net (code "61") (name "/PD3") (class "Default")
      (node (ref "J1") (pin "87") (pinfunction "PD3_87") (pintype "passive"))
      (node (ref "U1") (pin "84") (pinfunction "PD3/FSMC_CLK_84") (pintype "passive"))
    )
    (net (code "62") (name "/PD4") (class "Default")
      (node (ref "J1") (pin "86") (pinfunction "PD4_86") (pintype "passive"))
      (node (ref "U1") (pin "85") (pinfunction "PD4/FSMC_NOE_85") (pintype "passive"))
    )
    (net (code "63") (name "/PD5") (class "Default")
      (node (ref "J1") (pin "85") (pinfunction "PD5_85") (pintype "passive"))
      (node (ref "U1") (pin "86") (pinfunction "PD5/USART2_Tx/FSMC_NWE_86") (pintype "passive"))
    )
    (net (code "64") (name "/PD6") (class "Default")
      (node (ref "J1") (pin "84") (pinfunction "PD6_84") (pintype "passive"))
      (node (ref "U1") (pin "87") (pinfunction "PD6/USART2_Rx/FSMC_NWAIT_87") (pintype "passive"))
    )
    (net (code "65") (name "/PD7") (class "Default")
      (node (ref "J1") (pin "83") (pinfunction "PD7_83") (pintype "passive"))
      (node (ref "U1") (pin "88") (pinfunction "PD7/FSMC_NE1/FSMC_NCE2_88") (pintype "passive"))
    )
    (net (code "66") (name "/PD8") (class "Default")
      (node (ref "J1") (pin "41") (pinfunction "PD8_41") (pintype "passive"))
      (node (ref "U1") (pin "55") (pinfunction "PD8/USART3_Tx/FSMC_D13_55") (pintype "passive"))
    )
    (net (code "67") (name "/PD9") (class "Default")
      (node (ref "J1") (pin "42") (pinfunction "PD9_42") (pintype "passive"))
      (node (ref "U1") (pin "56") (pinfunction "PD9/USART3_Rx/FSMC_D14_56") (pintype "passive"))
    )
    (net (code "68") (name "/PD10") (class "Default")
      (node (ref "J1") (pin "43") (pinfunction "PD10_43") (pintype "passive"))
      (node (ref "U1") (pin "57") (pinfunction "PD10/FSMC_D15_57") (pintype "passive"))
    )
    (net (code "69") (name "/PD11") (class "Default")
      (node (ref "J1") (pin "44") (pinfunction "PD11_44") (pintype "passive"))
      (node (ref "U1") (pin "58") (pinfunction "PD11/FSMC_A16_58") (pintype "passive"))
    )
    (net (code "70") (name "/PD12") (class "Default")
      (node (ref "J1") (pin "45") (pinfunction "PD12_45") (pintype "passive"))
      (node (ref "U1") (pin "59") (pinfunction "PD12/T4C1/FSMC_A17_59") (pintype "passive"))
    )
    (net (code "71") (name "/PD13") (class "Default")
      (node (ref "J1") (pin "46") (pinfunction "PD13_46") (pintype "passive"))
      (node (ref "U1") (pin "60") (pinfunction "PD13/T4C2/FSMC_A18_60") (pintype "passive"))
    )
    (net (code "72") (name "/PD14") (class "Default")
      (node (ref "J1") (pin "47") (pinfunction "PD14_47") (pintype "passive"))
      (node (ref "U1") (pin "61") (pinfunction "PD14/T4C3/FSMC_D0_61") (pintype "passive"))
    )
    (net (code "73") (name "/PD15") (class "Default")
      (node (ref "J1") (pin "48") (pinfunction "PD15_48") (pintype "passive"))
      (node (ref "U1") (pin "62") (pinfunction "PD15/T4C4/FSMC_D1_62") (pintype "passive"))
    )
    (net (code "74") (name "/PE0") (class "Default")
      (node (ref "J1") (pin "73") (pinfunction "PE0_73") (pintype "passive"))
      (node (ref "U1") (pin "97") (pinfunction "PE0/T4_ETR/FSMC_NBL0_97") (pintype "passive"))
    )
    (net (code "75") (name "/PE1") (class "Default")
      (node (ref "J1") (pin "72") (pinfunction "PE1_72") (pintype "passive"))
      (node (ref "U1") (pin "98") (pinfunction "PE1/FSMC_NBL1_98") (pintype "passive"))
    )
    (net (code "76") (name "/PE2") (class "Default")
      (node (ref "J1") (pin "71") (pinfunction "PE2_71") (pintype "passive"))
      (node (ref "U1") (pin "1") (pinfunction "PE2/TRACECK/RSMC_A23_1") (pintype "passive"))
    )
    (net (code "77") (name "/PE3") (class "Default")
      (node (ref "J1") (pin "70") (pinfunction "PE3_70") (pintype "passive"))
      (node (ref "U1") (pin "2") (pinfunction "PE3/TRACED0/FSMC_A19_2") (pintype "passive"))
    )
    (net (code "78") (name "/PE4") (class "Default")
      (node (ref "J1") (pin "69") (pinfunction "PE4_69") (pintype "passive"))
      (node (ref "U1") (pin "3") (pinfunction "PE4/TRACED1/FSMC_A20_3") (pintype "passive"))
    )
    (net (code "79") (name "/PE5") (class "Default")
      (node (ref "J1") (pin "68") (pinfunction "PE5_68") (pintype "passive"))
      (node (ref "U1") (pin "4") (pinfunction "PE5/TRACED2/FSMC_A21_4") (pintype "passive"))
    )
    (net (code "80") (name "/PE6") (class "Default")
      (node (ref "J1") (pin "67") (pinfunction "PE6_67") (pintype "passive"))
      (node (ref "U1") (pin "5") (pinfunction "PE6/TRACED3/FSMC_A22_5") (pintype "passive"))
    )
    (net (code "81") (name "/PE7") (class "Default")
      (node (ref "J1") (pin "25") (pinfunction "PE7_25") (pintype "passive"))
      (node (ref "U1") (pin "38") (pinfunction "PE7/FSMC_D4/T1ETR_38") (pintype "passive"))
    )
    (net (code "82") (name "/PE8") (class "Default")
      (node (ref "J1") (pin "26") (pinfunction "PE8_26") (pintype "passive"))
      (node (ref "U1") (pin "39") (pinfunction "PE8/FSMC_D5/T1CH1N_39") (pintype "passive"))
    )
    (net (code "83") (name "/PE9") (class "Default")
      (node (ref "J1") (pin "27") (pinfunction "PE9_27") (pintype "passive"))
      (node (ref "U1") (pin "40") (pinfunction "PE9/FSMC_D6/T1C1_40") (pintype "passive"))
    )
    (net (code "84") (name "/PE10") (class "Default")
      (node (ref "J1") (pin "28") (pinfunction "PE10_28") (pintype "passive"))
      (node (ref "U1") (pin "41") (pinfunction "PE10/FSMC_D7/T1CH2N_41") (pintype "passive"))
    )
    (net (code "85") (name "/PE11") (class "Default")
      (node (ref "J1") (pin "29") (pinfunction "PE11_29") (pintype "passive"))
      (node (ref "U1") (pin "42") (pinfunction "PE11/FSMC_D8/T1C2_42") (pintype "passive"))
    )
    (net (code "86") (name "/PE12") (class "Default")
      (node (ref "J1") (pin "30") (pinfunction "PE12_30") (pintype "passive"))
      (node (ref "U1") (pin "43") (pinfunction "PE12/FSMC_D9/T1CH3N_43") (pintype "passive"))
    )
    (net (code "87") (name "/PE13") (class "Default")
      (node (ref "J1") (pin "31") (pinfunction "PE13_31") (pintype "passive"))
      (node (ref "U1") (pin "44") (pinfunction "PE13/FSMC_D10/T1C3_44") (pintype "passive"))
    )
    (net (code "88") (name "/PE14") (class "Default")
      (node (ref "J1") (pin "32") (pinfunction "PE14_32") (pintype "passive"))
      (node (ref "U1") (pin "45") (pinfunction "PE14/FSMC_D11/T1C4_45") (pintype "passive"))
    )
    (net (code "89") (name "/PE15") (class "Default")
      (node (ref "J1") (pin "33") (pinfunction "PE15_33") (pintype "passive"))
      (node (ref "U1") (pin "46") (pinfunction "PE15/FSMC_D12/T1BKIN_46") (pintype "passive"))
    )
    (net (code "90") (name "/TCKIN") (class "Default")
      (node (ref "P2") (pin "2") (pinfunction "2_2") (pintype "passive"))
      (node (ref "R6") (pin "1") (pinfunction "1_1") (pintype "passive"))
      (node (ref "U2") (pin "13") (pinfunction "PA3/ADC123_IN3/USART2_Rx/T5C4/T2C4_13") (pintype "passive"))
    )
    (net (code "91") (name "/TCKOUT") (class "Default")
      (node (ref "R6") (pin "2") (pinfunction "2_2") (pintype "passive"))
      (node (ref "U2") (pin "15") (pinfunction "PA5/ADC123_IN5/DAC_OUT2/SPI1_SCK_15") (pintype "passive"))
      (node (ref "U2") (pin "26") (pinfunction "PB13/I2S2_CK/T1CH1N/SPI2_SCK_26") (pintype "passive"))
    )
    (net (code "92") (name "/TDIIN") (class "Default")
      (node (ref "R4") (pin "1") (pinfunction "1_1") (pintype "passive"))
      (node (ref "U2") (pin "18") (pinfunction "PB0/ADC123_IN8/T3C3/T8C2N/T1C2N_18") (pintype "passive"))
    )
    (net (code "93") (name "/TDIOUT") (class "Default")
      (node (ref "R4") (pin "2") (pinfunction "2_2") (pintype "passive"))
      (node (ref "U2") (pin "27") (pinfunction "PB14/T1CH2N/SPI2_MISO_27") (pintype "passive"))
    )
    (net (code "94") (name "/TMSIN") (class "Default")
      (node (ref "P2") (pin "4") (pinfunction "4_4") (pintype "passive"))
      (node (ref "R5") (pin "1") (pinfunction "1_1") (pintype "passive"))
      (node (ref "U2") (pin "14") (pinfunction "PA4/ADC123_IN4/DAC_OUT1/SPI1_NSS_14") (pintype "passive"))
    )
    (net (code "95") (name "/TMSOUT") (class "Default")
      (node (ref "R5") (pin "2") (pinfunction "2_2") (pintype "passive"))
      (node (ref "U2") (pin "17") (pinfunction "PA7/ADC123_IN7/SPI1_MOSI/T8C1N/T3C2/T1C1N_17") (pintype "passive"))
    )
    (net (code "96") (name "/TRESIN") (class "Default")
      (node (ref "R7") (pin "1") (pinfunction "1_1") (pintype "passive"))
      (node (ref "U2") (pin "12") (pinfunction "PA2/ADC123_IN2/USART2_Tx/T5C3/T2C3_12") (pintype "passive"))
    )
    (net (code "97") (name "/TRESOUT") (class "Default")
      (node (ref "R7") (pin "2") (pinfunction "2_2") (pintype "passive"))
      (node (ref "U2") (pin "11") (pinfunction "PA1/ADC123_IN1/T5C2/T2C2_11") (pintype "passive"))
    )
    (net (code "98") (name "/TRSTIN") (class "Default")
      (node (ref "R3") (pin "1") (pinfunction "1_1") (pintype "passive"))
      (node (ref "U2") (pin "19") (pinfunction "PB1/ADC123_IN9/T3C4/T8C3N/T1C3N_19") (pintype "passive"))
    )
    (net (code "99") (name "/TRSTOUT") (class "Default")
      (node (ref "R3") (pin "2") (pinfunction "2_2") (pintype "passive"))
      (node (ref "U2") (pin "10") (pinfunction "PA0/WKUP/ADC123_IN0/T2C1ETR/T5C1/T8ETR_10") (pintype "passive"))
    )
    (net (code "100") (name "/UART_RX") (class "Default")
      (node (ref "P5") (pin "4") (pinfunction "4_4") (pintype "passive"))
      (node (ref "U5") (pin "4") (pinfunction "RXD_4") (pintype "passive"))
    )
    (net (code "101") (name "/UART_TX") (class "Default")
      (node (ref "P5") (pin "2") (pinfunction "2_2") (pintype "passive"))
      (node (ref "U5") (pin "3") (pinfunction "TXD_3") (pintype "passive"))
    )
    (net (code "102") (name "/USBD+") (class "Default")
      (node (ref "C8") (pin "1") (pinfunction "1_1") (pintype "passive"))
      (node (ref "R1") (pin "1") (pinfunction "1_1") (pintype "passive"))
      (node (ref "R9") (pin "1") (pinfunction "1_1") (pintype "passive"))
      (node (ref "USB1") (pin "3") (pinfunction "D+_3") (pintype "passive"))
    )
    (net (code "103") (name "/USBD-") (class "Default")
      (node (ref "C10") (pin "1") (pinfunction "1_1") (pintype "passive"))
      (node (ref "R8") (pin "1") (pinfunction "1_1") (pintype "passive"))
      (node (ref "USB1") (pin "2") (pinfunction "D-_2") (pintype "passive"))
    )
    (net (code "104") (name "/USBDM") (class "Default")
      (node (ref "R8") (pin "2") (pinfunction "2_2") (pintype "passive"))
      (node (ref "U2") (pin "32") (pinfunction "PA11/CAN_Rx/T1C4/USBDM_32") (pintype "passive"))
    )
    (net (code "105") (name "/USBDP") (class "Default")
      (node (ref "R9") (pin "2") (pinfunction "2_2") (pintype "passive"))
      (node (ref "U2") (pin "33") (pinfunction "PA12/CAN_Tx/T1ETR/USBDP_33") (pintype "passive"))
    )
    (net (code "106") (name "/VBAT") (class "Default")
      (node (ref "D2") (pin "2") (pinfunction "K_2") (pintype "passive"))
      (node (ref "D3") (pin "2") (pinfunction "K_2") (pintype "passive"))
      (node (ref "U1") (pin "6") (pinfunction "VBAT_6") (pintype "passive"))
    )
    (net (code "107") (name "/VBAT_IN") (class "Default")
      (node (ref "BT1") (pin "1") (pinfunction "+_1") (pintype "passive"))
      (node (ref "D3") (pin "1") (pinfunction "A_1") (pintype "passive"))
      (node (ref "J1") (pin "10") (pinfunction "VBAT_10") (pintype "passive"))
    )
    (net (code "108") (name "/VREF+") (class "Default")
      (node (ref "C29") (pin "2") (pinfunction "2_2") (pintype "passive"))
      (node (ref "J1") (pin "8") (pinfunction "VREF+_8") (pintype "passive"))
      (node (ref "P3") (pin "1") (pinfunction "1_1") (pintype "passive"))
      (node (ref "U1") (pin "21") (pinfunction "VREF+_21") (pintype "passive"))
    )
    (net (code "109") (name "Net-(D0-A)") (class "Default")
      (node (ref "D0") (pin "1") (pinfunction "A_1") (pintype "passive"))
      (node (ref "F1") (pin "2") (pinfunction "2_2") (pintype "passive"))
      (node (ref "P0") (pin "1") (pinfunction "1_1") (pintype "passive"))
    )
    (net (code "110") (name "Net-(D1-K)") (class "Default")
      (node (ref "D1") (pin "2") (pinfunction "K_2") (pintype "passive"))
      (node (ref "R2") (pin "1") (pinfunction "1_1") (pintype "passive"))
    )
    (net (code "111") (name "Net-(D5-A)") (class "Default")
      (node (ref "D5") (pin "1") (pinfunction "A_1") (pintype "passive"))
      (node (ref "R18") (pin "2") (pinfunction "2_2") (pintype "passive"))
    )
    (net (code "112") (name "Net-(D6-A)") (class "Default")
      (node (ref "D6") (pin "1") (pinfunction "A_1") (pintype "passive"))
      (node (ref "R19") (pin "2") (pinfunction "2_2") (pintype "passive"))
    )
    (net (code "113") (name "Net-(P4-Pad2)") (class "Default")
      (node (ref "P4") (pin "2") (pinfunction "2_2") (pintype "passive"))
      (node (ref "R18") (pin "1") (pinfunction "1_1") (pintype "passive"))
    )
    (net (code "114") (name "Net-(P4-Pad4)") (class "Default")
      (node (ref "P4") (pin "4") (pinfunction "4_4") (pintype "passive"))
      (node (ref "R19") (pin "1") (pinfunction "1_1") (pintype "passive"))
    )
    (net (code "115") (name "Net-(U1B-OSC_IN)") (class "Default")
      (node (ref "C24") (pin "1") (pinfunction "1_1") (pintype "passive"))
      (node (ref "U1") (pin "12") (pinfunction "OSC_IN_12") (pintype "passive"))
      (node (ref "XTAL3") (pin "1") (pinfunction "1_1") (pintype "passive"))
    )
    (net (code "116") (name "Net-(U1B-OSC_OUT)") (class "Default")
      (node (ref "C23") (pin "1") (pinfunction "1_1") (pintype "passive"))
      (node (ref "U1") (pin "13") (pinfunction "OSC_OUT_13") (pintype "passive"))
      (node (ref "XTAL3") (pin "2") (pinfunction "2_2") (pintype "passive"))
    )
    (net (code "117") (name "Net-(U1B-PDR_ON)") (class "Default")
      (node (ref "R20") (pin "1") (pinfunction "1_1") (pintype "passive"))
      (node (ref "R21") (pin "1") (pinfunction "1_1") (pintype "passive"))
      (node (ref "U1") (pin "99") (pinfunction "PDR_ON_99") (pintype "passive"))
    )
    (net (code "118") (name "Net-(U1B-VCAP1)") (class "Default")
      (node (ref "C20") (pin "2") (pinfunction "2_2") (pintype "passive"))
      (node (ref "R22") (pin "1") (pinfunction "1_1") (pintype "passive"))
      (node (ref "U1") (pin "49") (pinfunction "VCAP1_49") (pintype "passive"))
    )
    (net (code "119") (name "Net-(U1B-VCAP2)") (class "Default")
      (node (ref "C22") (pin "2") (pinfunction "2_2") (pintype "passive"))
      (node (ref "U1") (pin "73") (pinfunction "VCAP2_73") (pintype "passive"))
    )
    (net (code "120") (name "Net-(U1B-VDD12)") (class "Default")
      (node (ref "R11") (pin "1") (pinfunction "1_1") (pintype "passive"))
      (node (ref "R12") (pin "1") (pinfunction "1_1") (pintype "passive"))
      (node (ref "U1") (pin "19") (pinfunction "VDD12_19") (pintype "passive"))
    )
    (net (code "121") (name "Net-(U2-OSC_IN)") (class "Default")
      (node (ref "C1") (pin "1") (pinfunction "1_1") (pintype "passive"))
      (node (ref "U2") (pin "5") (pinfunction "OSC_IN_5") (pintype "passive"))
      (node (ref "XTAL1") (pin "1") (pinfunction "1_1") (pintype "passive"))
    )
    (net (code "122") (name "Net-(U2-OSC_OUT)") (class "Default")
      (node (ref "C2") (pin "1") (pinfunction "1_1") (pintype "passive"))
      (node (ref "U2") (pin "6") (pinfunction "OSC_OUT_6") (pintype "passive"))
      (node (ref "XTAL1") (pin "2") (pinfunction "2_2") (pintype "passive"))
    )
    (net (code "123") (name "Net-(U3-BP)") (class "Default")
      (node (ref "C12") (pin "1") (pinfunction "1_1") (pintype "passive"))
      (node (ref "U3") (pin "4") (pinfunction "BP_4") (pintype "passive"))
    )
    (net (code "124") (name "Net-(U3-EN)") (class "Default")
      (node (ref "C11") (pin "2") (pinfunction "2_2") (pintype "passive"))
      (node (ref "P0") (pin "2") (pinfunction "2_2") (pintype "passive"))
      (node (ref "U3") (pin "1") (pinfunction "VIN_1") (pintype "passive"))
      (node (ref "U3") (pin "3") (pinfunction "EN_3") (pintype "passive"))
    )
    (net (code "125") (name "Net-(U5-UD+)") (class "Default")
      (node (ref "U5") (pin "6") (pinfunction "UD+_6") (pintype "passive"))
      (node (ref "USB2") (pin "3") (pinfunction "D+_3") (pintype "passive"))
    )
    (net (code "126") (name "Net-(U5-UD-)") (class "Default")
      (node (ref "U5") (pin "7") (pinfunction "UD-_7") (pintype "passive"))
      (node (ref "USB2") (pin "2") (pinfunction "D-_2") (pintype "passive"))
    )
    (net (code "127") (name "Net-(U5-V3)") (class "Default")
      (node (ref "C31") (pin "2") (pinfunction "2_2") (pintype "passive"))
      (node (ref "U5") (pin "5") (pinfunction "V3_5") (pintype "passive"))
    )
    (net (code "128") (name "Net-(U5-XI)") (class "Default")
      (node (ref "C32") (pin "2") (pinfunction "2_2") (pintype "passive"))
      (node (ref "U5") (pin "9") (pinfunction "XI_9") (pintype "passive"))
      (node (ref "XTAL4") (pin "2") (pinfunction "2_2") (pintype "passive"))
    )
    (net (code "129") (name "Net-(U5-XO)") (class "Default")
      (node (ref "C33") (pin "2") (pinfunction "2_2") (pintype "passive"))
      (node (ref "U5") (pin "10") (pinfunction "XO_10") (pintype "passive"))
      (node (ref "XTAL4") (pin "1") (pinfunction "1_1") (pintype "passive"))
    )
    (net (code "130") (name "VDD") (class "Default")
      (node (ref "C15") (pin "2") (pinfunction "2_2") (pintype "passive"))
      (node (ref "C16") (pin "2") (pinfunction "2_2") (pintype "passive"))
      (node (ref "C17") (pin "2") (pinfunction "2_2") (pintype "passive"))
      (node (ref "C18") (pin "2") (pinfunction "2_2") (pintype "passive"))
      (node (ref "C19") (pin "2") (pinfunction "2_2") (pintype "passive"))
      (node (ref "C26") (pin "1") (pinfunction "1_1") (pintype "passive"))
      (node (ref "C28") (pin "2") (pinfunction "2_2") (pintype "passive"))
      (node (ref "D2") (pin "1") (pinfunction "A_1") (pintype "passive"))
      (node (ref "J1") (pin "49") (pinfunction "VDD_49") (pintype "passive"))
      (node (ref "J1") (pin "53") (pinfunction "VDD_53") (pintype "passive"))
      (node (ref "J1") (pin "54") (pinfunction "VDD_54") (pintype "passive"))
      (node (ref "P3") (pin "2") (pinfunction "2_2") (pintype "passive"))
      (node (ref "R11") (pin "2") (pinfunction "2_2") (pintype "passive"))
      (node (ref "R13") (pin "1") (pinfunction "1_1") (pintype "passive"))
      (node (ref "R16") (pin "1") (pinfunction "1_1") (pintype "passive"))
      (node (ref "R21") (pin "2") (pinfunction "2_2") (pintype "passive"))
      (node (ref "S1") (pin "1") (pinfunction "A1_1") (pintype "passive"))
      (node (ref "S1") (pin "2") (pinfunction "A2_2") (pintype "passive"))
      (node (ref "U1") (pin "100") (pinfunction "VDD_3_100") (pintype "passive"))
      (node (ref "U1") (pin "11") (pinfunction "VDD_5_11") (pintype "passive"))
      (node (ref "U1") (pin "28") (pinfunction "VDD_4_28") (pintype "passive"))
      (node (ref "U1") (pin "50") (pinfunction "VDD_1_50") (pintype "passive"))
      (node (ref "U1") (pin "75") (pinfunction "VDD_2_75") (pintype "passive"))
      (node (ref "U4") (pin "2") (pinfunction "VOUT_2") (pintype "passive"))
    )
    (net (code "131") (name "VDD5V") (class "Default")
      (node (ref "C25") (pin "1") (pinfunction "1_1") (pintype "passive"))
      (node (ref "C27") (pin "2") (pinfunction "2_2") (pintype "passive"))
      (node (ref "D0") (pin "2") (pinfunction "K_2") (pintype "passive"))
      (node (ref "D4") (pin "2") (pinfunction "K_2") (pintype "passive"))
      (node (ref "J1") (pin "51") (pinfunction "VDD5V_51") (pintype "passive"))
      (node (ref "J1") (pin "52") (pinfunction "VDD5V_52") (pintype "passive"))
      (node (ref "U4") (pin "3") (pinfunction "VIN_3") (pintype "passive"))
    )
    (net (code "132") (name "VDDA") (class "Default")
      (node (ref "J1") (pin "9") (pinfunction "VDDA_9") (pintype "passive"))
      (node (ref "R13") (pin "2") (pinfunction "2_2") (pintype "passive"))
      (node (ref "U1") (pin "22") (pinfunction "VDDA_22") (pintype "passive"))
    )
    (net (code "133") (name "VDD_DBG") (class "Default")
      (node (ref "C4") (pin "1") (pinfunction "1_1") (pintype "passive"))
      (node (ref "C5") (pin "1") (pinfunction "1_1") (pintype "passive"))
      (node (ref "C6") (pin "1") (pinfunction "1_1") (pintype "passive"))
      (node (ref "C7") (pin "1") (pinfunction "1_1") (pintype "passive"))
      (node (ref "C9") (pin "1") (pinfunction "1_1") (pintype "passive"))
      (node (ref "D1") (pin "1") (pinfunction "A_1") (pintype "passive"))
      (node (ref "R10") (pin "2") (pinfunction "2_2") (pintype "passive"))
      (node (ref "U2") (pin "1") (pinfunction "VBAT_1") (pintype "passive"))
      (node (ref "U2") (pin "24") (pinfunction "VDD_1_24") (pintype "passive"))
      (node (ref "U2") (pin "36") (pinfunction "VDD_2_36") (pintype "passive"))
      (node (ref "U2") (pin "48") (pinfunction "VDD_3_48") (pintype "passive"))
      (node (ref "U2") (pin "9") (pinfunction "VDDA_9") (pintype "passive"))
      (node (ref "U3") (pin "5") (pinfunction "VOUT_5") (pintype "passive"))
    )
    (net (code "134") (name "VDD_UART") (class "Default")
      (node (ref "C30") (pin "1") (pinfunction "1_1") (pintype "passive"))
      (node (ref "C34") (pin "1") (pinfunction "1_1") (pintype "passive"))
      (node (ref "D4") (pin "1") (pinfunction "A_1") (pintype "passive"))
      (node (ref "U5") (pin "19") (pinfunction "VCC_19") (pintype "passive"))
      (node (ref "USB2") (pin "1") (pinfunction "VCC_1") (pintype "passive"))
    )
    (net (code "135") (name "VDD_USB") (class "Default")
      (node (ref "F1") (pin "1") (pinfunction "1_1") (pintype "passive"))
      (node (ref "USB1") (pin "1") (pinfunction "VCC_1") (pintype "passive"))
    )
    (net (code "136") (name "VSS") (class "Default")
      (node (ref "BT1") (pin "2") (pinfunction "-_2") (pintype "passive"))
      (node (ref "C1") (pin "2") (pinfunction "2_2") (pintype "passive"))
      (node (ref "C10") (pin "2") (pinfunction "2_2") (pintype "passive"))
      (node (ref "C11") (pin "1") (pinfunction "1_1") (pintype "passive"))
      (node (ref "C12") (pin "2") (pinfunction "2_2") (pintype "passive"))
      (node (ref "C13") (pin "2") (pinfunction "2_2") (pintype "passive"))
      (node (ref "C14") (pin "2") (pinfunction "2_2") (pintype "passive"))
      (node (ref "C15") (pin "1") (pinfunction "1_1") (pintype "passive"))
      (node (ref "C16") (pin "1") (pinfunction "1_1") (pintype "passive"))
      (node (ref "C17") (pin "1") (pinfunction "1_1") (pintype "passive"))
      (node (ref "C18") (pin "1") (pinfunction "1_1") (pintype "passive"))
      (node (ref "C19") (pin "1") (pinfunction "1_1") (pintype "passive"))
      (node (ref "C2") (pin "2") (pinfunction "2_2") (pintype "passive"))
      (node (ref "C20") (pin "1") (pinfunction "1_1") (pintype "passive"))
      (node (ref "C21") (pin "2") (pinfunction "2_2") (pintype "passive"))
      (node (ref "C22") (pin "1") (pinfunction "1_1") (pintype "passive"))
      (node (ref "C23") (pin "2") (pinfunction "2_2") (pintype "passive"))
      (node (ref "C24") (pin "2") (pinfunction "2_2") (pintype "passive"))
      (node (ref "C25") (pin "2") (pinfunction "2_2") (pintype "passive"))
      (node (ref "C26") (pin "2") (pinfunction "2_2") (pintype "passive"))
      (node (ref "C27") (pin "1") (pinfunction "1_1") (pintype "passive"))
      (node (ref "C28") (pin "1") (pinfunction "1_1") (pintype "passive"))
      (node (ref "C3") (pin "2") (pinfunction "2_2") (pintype "passive"))
      (node (ref "C30") (pin "2") (pinfunction "2_2") (pintype "passive"))
      (node (ref "C31") (pin "1") (pinfunction "1_1") (pintype "passive"))
      (node (ref "C32") (pin "1") (pinfunction "1_1") (pintype "passive"))
      (node (ref "C33") (pin "1") (pinfunction "1_1") (pintype "passive"))
      (node (ref "C34") (pin "2") (pinfunction "2_2") (pintype "passive"))
      (node (ref "C4") (pin "2") (pinfunction "2_2") (pintype "passive"))
      (node (ref "C5") (pin "2") (pinfunction "2_2") (pintype "passive"))
      (node (ref "C6") (pin "2") (pinfunction "2_2") (pintype "passive"))
      (node (ref "C7") (pin "2") (pinfunction "2_2") (pintype "passive"))
      (node (ref "C8") (pin "2") (pinfunction "2_2") (pintype "passive"))
      (node (ref "C9") (pin "2") (pinfunction "2_2") (pintype "passive"))
      (node (ref "D5") (pin "2") (pinfunction "K_2") (pintype "passive"))
      (node (ref "D6") (pin "2") (pinfunction "K_2") (pintype "passive"))
      (node (ref "J1") (pin "1") (pinfunction "VSS_1") (pintype "passive"))
      (node (ref "J1") (pin "100") (pinfunction "VSS_100") (pintype "passive"))
      (node (ref "J1") (pin "24") (pinfunction "VSS_24") (pintype "passive"))
      (node (ref "J1") (pin "34") (pinfunction "VSS_34") (pintype "passive"))
      (node (ref "J1") (pin "50") (pinfunction "VSS_50") (pintype "passive"))
      (node (ref "J1") (pin "55") (pinfunction "VSS_55") (pintype "passive"))
      (node (ref "J1") (pin "56") (pinfunction "VSS_56") (pintype "passive"))
      (node (ref "J1") (pin "74") (pinfunction "VSS_74") (pintype "passive"))
      (node (ref "J1") (pin "99") (pinfunction "VSS_99") (pintype "passive"))
      (node (ref "K1") (pin "1") (pinfunction "1_1") (pintype "passive"))
      (node (ref "K2") (pin "1") (pinfunction "1_1") (pintype "passive"))
      (node (ref "P1") (pin "2") (pinfunction "2_2") (pintype "passive"))
      (node (ref "R0") (pin "2") (pinfunction "2_2") (pintype "passive"))
      (node (ref "R12") (pin "2") (pinfunction "2_2") (pintype "passive"))
      (node (ref "R14") (pin "1") (pinfunction "1_1") (pintype "passive"))
      (node (ref "R15") (pin "1") (pinfunction "1_1") (pintype "passive"))
      (node (ref "R17") (pin "1") (pinfunction "1_1") (pintype "passive"))
      (node (ref "R20") (pin "2") (pinfunction "2_2") (pintype "passive"))
      (node (ref "R22") (pin "2") (pinfunction "2_2") (pintype "passive"))
      (node (ref "U1") (pin "10") (pinfunction "VSS_5_10") (pintype "passive"))
      (node (ref "U1") (pin "27") (pinfunction "VSS_4_27") (pintype "passive"))
      (node (ref "U1") (pin "74") (pinfunction "VSS_2_74") (pintype "passive"))
      (node (ref "U2") (pin "20") (pinfunction "PB2/BOOT1_20") (pintype "passive"))
      (node (ref "U2") (pin "23") (pinfunction "VSS_1_23") (pintype "passive"))
      (node (ref "U2") (pin "35") (pinfunction "VSS_2_35") (pintype "passive"))
      (node (ref "U2") (pin "47") (pinfunction "VSS_3_47") (pintype "passive"))
      (node (ref "U2") (pin "8") (pinfunction "VSSA_8") (pintype "passive"))
      (node (ref "U3") (pin "2") (pinfunction "GND_2") (pintype "passive"))
      (node (ref "U4") (pin "1") (pinfunction "GND_1") (pintype "passive"))
      (node (ref "U5") (pin "8") (pinfunction "GND_8") (pintype "passive"))
      (node (ref "USB1") (pin "5") (pinfunction "GND_5") (pintype "passive"))
      (node (ref "USB2") (pin "5") (pinfunction "GND_5") (pintype "passive"))
    )
    (net (code "137") (name "VSSA") (class "Default")
      (node (ref "C29") (pin "1") (pinfunction "1_1") (pintype "passive"))
      (node (ref "J1") (pin "7") (pinfunction "VSSA_7") (pintype "passive"))
      (node (ref "R14") (pin "2") (pinfunction "2_2") (pintype "passive"))
      (node (ref "U1") (pin "20") (pinfunction "VSSA_20") (pintype "passive"))
    )
    (net (code "138") (name "unconnected-(U2-PA8{slash}T1C1{slash}MCO-Pad29)") (class "Default")
      (node (ref "U2") (pin "29") (pinfunction "PA8/T1C1/MCO_29") (pintype "passive+no_connect"))
    )
    (net (code "139") (name "unconnected-(U2-PA15{slash}JTDI{slash}I2S3_WS{slash}JTDI{slash}T2C1ETR{slash}SPI3_NSS-Pad38)") (class "Default")
      (node (ref "U2") (pin "38") (pinfunction "PA15/JTDI/I2S3_WS/JTDI/T2C1ETR/SPI3_NSS_38") (pintype "passive+no_connect"))
    )
    (net (code "140") (name "unconnected-(U2-PB3{slash}JTDO{slash}SPI3_SCK{slash}I2S3_CK{slash}T2C2{slash}SPI1_SCK-Pad39)") (class "Default")
      (node (ref "U2") (pin "39") (pinfunction "PB3/JTDO/SPI3_SCK/I2S3_CK/T2C2/SPI1_SCK_39") (pintype "passive+no_connect"))
    )
    (net (code "141") (name "unconnected-(U2-PB4{slash}NJTRST{slash}SPI3_MISO{slash}T3C1{slash}SPI1_MISO-Pad40)") (class "Default")
      (node (ref "U2") (pin "40") (pinfunction "PB4/NJTRST/SPI3_MISO/T3C1/SPI1_MISO_40") (pintype "passive+no_connect"))
    )
    (net (code "142") (name "unconnected-(U2-PB5{slash}I2C1_SMBA{slash}I2S3_SD{slash}SPI3_MOSI{slash}T3C2{slash}SPI1_MOSI-Pad41)") (class "Default")
      (node (ref "U2") (pin "41") (pinfunction "PB5/I2C1_SMBA/I2S3_SD/SPI3_MOSI/T3C2/SPI1_MOSI_41") (pintype "passive+no_connect"))
    )
    (net (code "143") (name "unconnected-(U2-PB6{slash}I2C1_SCL{slash}T4C1{slash}USART1_Tx-Pad42)") (class "Default")
      (node (ref "U2") (pin "42") (pinfunction "PB6/I2C1_SCL/T4C1/USART1_Tx_42") (pintype "passive+no_connect"))
    )
    (net (code "144") (name "unconnected-(U2-PB7{slash}I2C1_SDA{slash}FSMC_NADV{slash}USART1_Rx-Pad43)") (class "Default")
      (node (ref "U2") (pin "43") (pinfunction "PB7/I2C1_SDA/FSMC_NADV/USART1_Rx_43") (pintype "passive+no_connect"))
    )
    (net (code "145") (name "unconnected-(U2-PB8{slash}SDIO_D4{slash}I2C1_SCL{slash}T4C3(7){slash}CAN_Rx-Pad45)") (class "Default")
      (node (ref "U2") (pin "45") (pinfunction "PB8/SDIO_D4/I2C1_SCL/T4C3(7)/CAN_Rx_45") (pintype "passive+no_connect"))
    )
    (net (code "146") (name "unconnected-(U2-PB9{slash}SDIO_D5{slash}I2C1_SDA{slash}T4C4{slash}CAN_Tx-Pad46)") (class "Default")
      (node (ref "U2") (pin "46") (pinfunction "PB9/SDIO_D5/I2C1_SDA/T4C4/CAN_Tx_46") (pintype "passive+no_connect"))
    )
    (net (code "147") (name "unconnected-(U2-PB10{slash}USART3_Tx{slash}I2C2_SCL{slash}T2C3-Pad21)") (class "Default")
      (node (ref "U2") (pin "21") (pinfunction "PB10/USART3_Tx/I2C2_SCL/T2C3_21") (pintype "passive+no_connect"))
    )
    (net (code "148") (name "unconnected-(U2-PB11{slash}USART3_Rx{slash}I2C2_SDA{slash}T2C4-Pad22)") (class "Default")
      (node (ref "U2") (pin "22") (pinfunction "PB11/USART3_Rx/I2C2_SDA/T2C4_22") (pintype "passive+no_connect"))
    )
    (net (code "149") (name "unconnected-(U2-PC13-TAMPER-RTC-Pad2)") (class "Default")
      (node (ref "U2") (pin "2") (pinfunction "PC13-TAMPER-RTC_2") (pintype "passive+no_connect"))
    )
    (net (code "150") (name "unconnected-(U2-PC14-OSC32_IN-Pad3)") (class "Default")
      (node (ref "U2") (pin "3") (pinfunction "PC14-OSC32_IN_3") (pintype "passive+no_connect"))
    )
    (net (code "151") (name "unconnected-(U2-PC15-OSC32_OUT-Pad4)") (class "Default")
      (node (ref "U2") (pin "4") (pinfunction "PC15-OSC32_OUT_4") (pintype "passive+no_connect"))
    )
    (net (code "152") (name "unconnected-(U5-ACT-Pad2)") (class "Default")
      (node (ref "U5") (pin "2") (pinfunction "ACT_2") (pintype "passive+no_connect"))
    )
    (net (code "153") (name "unconnected-(U5-CK0-Pad1)") (class "Default")
      (node (ref "U5") (pin "1") (pinfunction "CK0_1") (pintype "passive+no_connect"))
    )
    (net (code "154") (name "unconnected-(U5-CTS-Pad11)") (class "Default")
      (node (ref "U5") (pin "11") (pinfunction "CTS_11") (pintype "passive+no_connect"))
    )
    (net (code "155") (name "unconnected-(U5-DCD-Pad14)") (class "Default")
      (node (ref "U5") (pin "14") (pinfunction "DCD_14") (pintype "passive+no_connect"))
    )
    (net (code "156") (name "unconnected-(U5-DSR-Pad12)") (class "Default")
      (node (ref "U5") (pin "12") (pinfunction "DSR_12") (pintype "passive+no_connect"))
    )
    (net (code "157") (name "unconnected-(U5-DTR-Pad15)") (class "Default")
      (node (ref "U5") (pin "15") (pinfunction "DTR_15") (pintype "passive+no_connect"))
    )
    (net (code "158") (name "unconnected-(U5-NC-Pad17)") (class "Default")
      (node (ref "U5") (pin "17") (pinfunction "NC_17") (pintype "passive+no_connect"))
    )
    (net (code "159") (name "unconnected-(U5-NOS-Pad20)") (class "Default")
      (node (ref "U5") (pin "20") (pinfunction "NOS_20") (pintype "passive+no_connect"))
    )
    (net (code "160") (name "unconnected-(U5-R232-Pad18)") (class "Default")
      (node (ref "U5") (pin "18") (pinfunction "R232_18") (pintype "passive+no_connect"))
    )
    (net (code "161") (name "unconnected-(U5-RI-Pad13)") (class "Default")
      (node (ref "U5") (pin "13") (pinfunction "RI_13") (pintype "passive+no_connect"))
    )
    (net (code "162") (name "unconnected-(U5-RTS-Pad16)") (class "Default")
      (node (ref "U5") (pin "16") (pinfunction "RTS_16") (pintype "passive+no_connect"))
    )
    (net (code "163") (name "unconnected-(USB1-OTG-Pad4)") (class "Default")
      (node (ref "USB1") (pin "4") (pinfunction "OTG_4") (pintype "passive+no_connect"))
    )
    (net (code "164") (name "unconnected-(USB1-Shell-Pad6)") (class "Default")
      (node (ref "USB1") (pin "6") (pinfunction "Shell_6") (pintype "passive+no_connect"))
    )
    (net (code "165") (name "unconnected-(USB2-OTG-Pad4)") (class "Default")
      (node (ref "USB2") (pin "4") (pinfunction "OTG_4") (pintype "passive+no_connect"))
    )
    (net (code "166") (name "unconnected-(USB2-Shell-Pad6)") (class "Default")
      (node (ref "USB2") (pin "6") (pinfunction "Shell_6") (pintype "passive+no_connect"))
    )
  )
)
